# Sheet2_W5500.net
KiCad netlist of a schematic drawn in Altium Designer
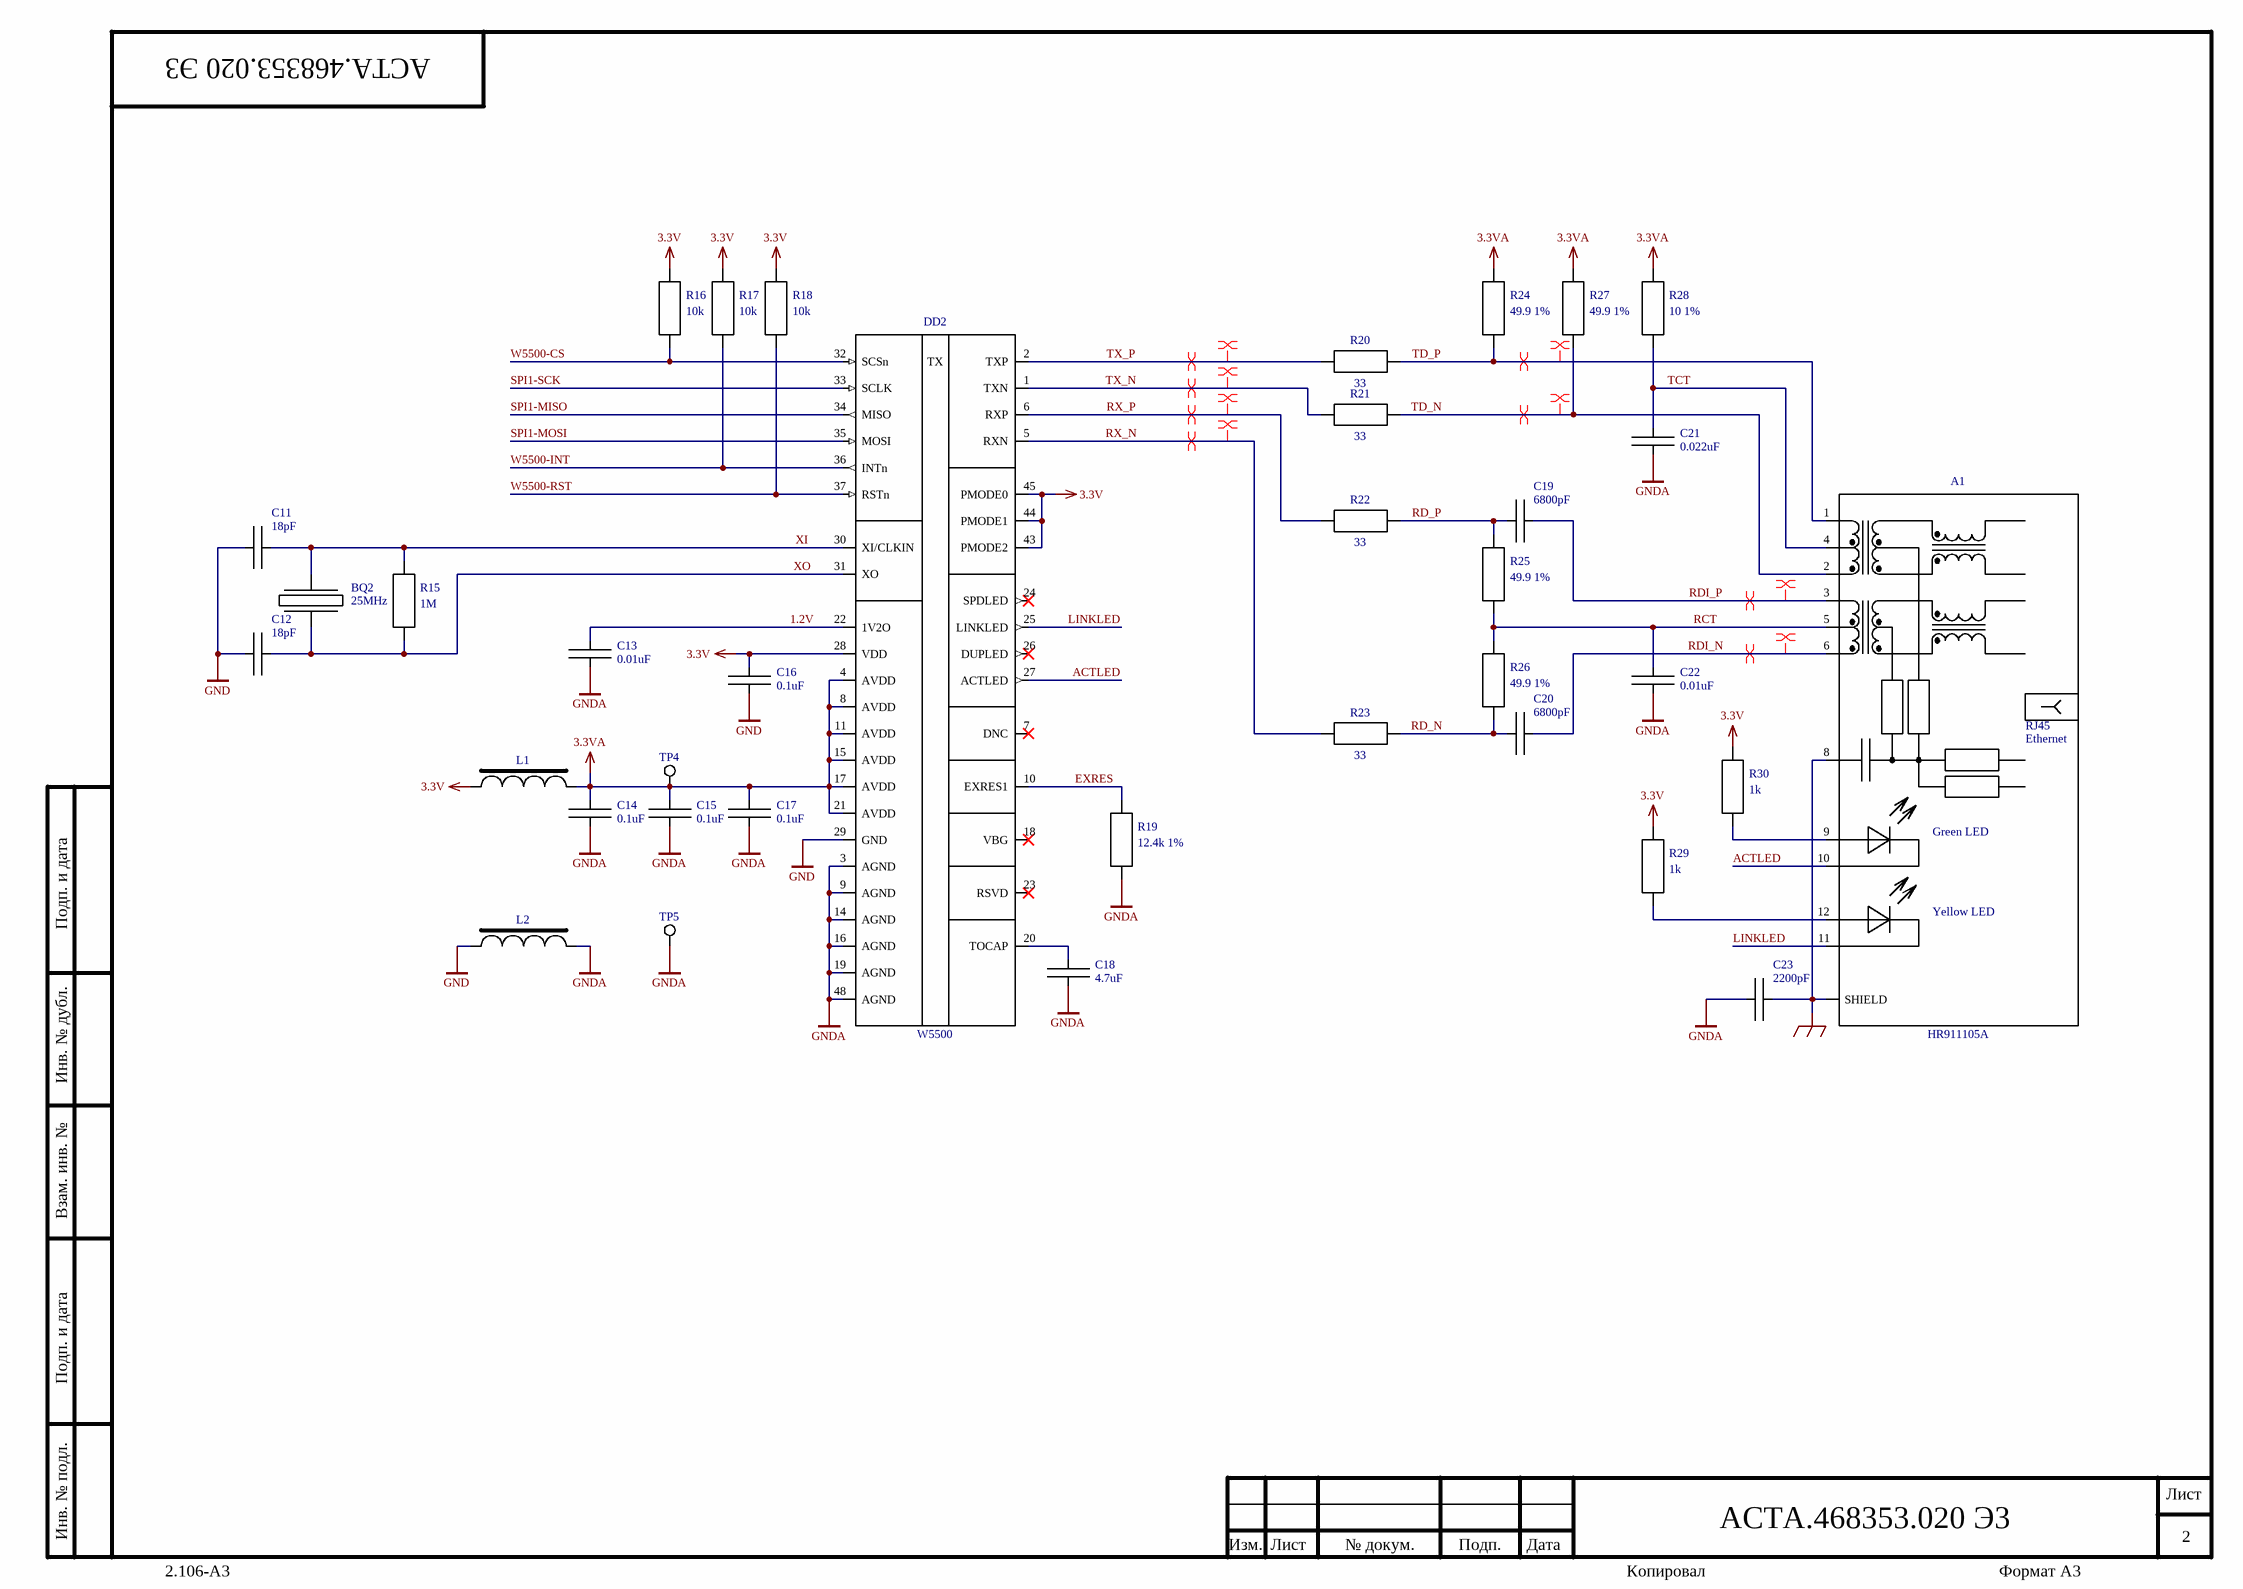
[diagram p0: Sheet2_W5500.SchDoc]

(export (version "E")
  (design (tool "Eeschema 10.0.6"))
  (components
    (comp (ref "A1")
      (value "HR911105A")
      (footprint "HR911105A")
      (description "Ethernet Connector 10/100 1x1 Tab Down RJ45 w/mag G/Y LED")
      (libsource (lib "Devices") (part "HR911105A"))
    )
    (comp (ref "BQ2")
      (value "25MHz")
      (footprint "HT-49S")
      (fields (field (name "Comment") "HT-49S_Rated"))
      (libsource (lib "Resonators") (part "HT-49S_Rated"))
    )
    (comp (ref "C11")
      (value "18pF")
      (footprint "CAP0805")
      (fields (field (name "Comment") "CAP0805_Rated"))
      (libsource (lib "Ceramic_Capacitors") (part "CAP0805_Rated"))
    )
    (comp (ref "C12")
      (value "18pF")
      (footprint "CAP0805")
      (fields (field (name "Comment") "CAP0805_Rated"))
      (libsource (lib "Ceramic_Capacitors") (part "CAP0805_Rated"))
    )
    (comp (ref "C13")
      (value "0.01uF")
      (footprint "CAP0805")
      (fields (field (name "Comment") "CAP0805_Rated"))
      (libsource (lib "Ceramic_Capacitors") (part "CAP0805_Rated"))
    )
    (comp (ref "C14")
      (value "0.1uF")
      (footprint "CAP0805")
      (fields (field (name "Comment") "CAP0805_Rated"))
      (libsource (lib "Ceramic_Capacitors") (part "CAP0805_Rated"))
    )
    (comp (ref "C15")
      (value "0.1uF")
      (footprint "CAP0805")
      (fields (field (name "Comment") "CAP0805_Rated"))
      (libsource (lib "Ceramic_Capacitors") (part "CAP0805_Rated"))
    )
    (comp (ref "C16")
      (value "0.1uF")
      (footprint "CAP0805")
      (fields (field (name "Comment") "CAP0805_Rated"))
      (libsource (lib "Ceramic_Capacitors") (part "CAP0805_Rated"))
    )
    (comp (ref "C17")
      (value "0.1uF")
      (footprint "CAP0805")
      (fields (field (name "Comment") "CAP0805_Rated"))
      (libsource (lib "Ceramic_Capacitors") (part "CAP0805_Rated"))
    )
    (comp (ref "C18")
      (value "4.7uF")
      (footprint "CAP1206")
      (fields (field (name "Comment") "CAP1206_Rated"))
      (libsource (lib "Ceramic_Capacitors") (part "CAP1206_Rated"))
    )
    (comp (ref "C19")
      (value "6800pF")
      (footprint "CAP0805")
      (fields (field (name "Comment") "CAP0805_Rated"))
      (libsource (lib "Ceramic_Capacitors") (part "CAP0805_Rated"))
    )
    (comp (ref "C20")
      (value "6800pF")
      (footprint "CAP0805")
      (fields (field (name "Comment") "CAP0805_Rated"))
      (libsource (lib "Ceramic_Capacitors") (part "CAP0805_Rated"))
    )
    (comp (ref "C21")
      (value "0.022uF")
      (footprint "CAP0805")
      (fields (field (name "Comment") "CAP0805_Rated"))
      (libsource (lib "Ceramic_Capacitors") (part "CAP0805_Rated"))
    )
    (comp (ref "C22")
      (value "0.01uF")
      (footprint "CAP0805")
      (fields (field (name "Comment") "CAP0805_Rated"))
      (libsource (lib "Ceramic_Capacitors") (part "CAP0805_Rated"))
    )
    (comp (ref "C23")
      (value "2200pF")
      (footprint "CAP1812")
      (fields (field (name "Comment") "CAP1812_Rated"))
      (libsource (lib "Ceramic_Capacitors") (part "CAP1812_Rated"))
    )
    (comp (ref "DD2")
      (value "W5500")
      (footprint "LQFP-48")
      (description "Ethernet ICs 3in1 Enet Controller TCP/IP +MAC+PHY")
      (libsource (lib "Interface_ICs") (part "W5500"))
    )
    (comp (ref "L1")
      (value "BLM21BD121SN1D")
      (footprint "IND0805")
      (description "Ferrite Bead 0805 120 Ohm")
      (fields (field (name "MANUFACTURER") "Murata") (field (name "TOLERANCE") "25%"))
      (libsource (lib "Inductors") (part "BLM21BD121SN1D"))
    )
    (comp (ref "L2")
      (value "BLM21BD121SN1D")
      (footprint "IND0805")
      (description "Ferrite Bead 0805 120 Ohm")
      (fields (field (name "MANUFACTURER") "Murata") (field (name "TOLERANCE") "25%"))
      (libsource (lib "Inductors") (part "BLM21BD121SN1D"))
    )
    (comp (ref "R15")
      (value "1M")
      (footprint "RES0805")
      (fields (field (name "TOLERANCE") "5%") (field (name "Comment") "RES0805_Rated"))
      (libsource (lib "Resistors") (part "RES0805_Rated"))
    )
    (comp (ref "R16")
      (value "10k")
      (footprint "RES0805")
      (fields (field (name "TOLERANCE") "5%") (field (name "Comment") "RES0805_Rated"))
      (libsource (lib "Resistors") (part "RES0805_Rated"))
    )
    (comp (ref "R17")
      (value "10k")
      (footprint "RES0805")
      (fields (field (name "TOLERANCE") "5%") (field (name "Comment") "RES0805_Rated"))
      (libsource (lib "Resistors") (part "RES0805_Rated"))
    )
    (comp (ref "R18")
      (value "10k")
      (footprint "RES0805")
      (fields (field (name "TOLERANCE") "5%") (field (name "Comment") "RES0805_Rated"))
      (libsource (lib "Resistors") (part "RES0805_Rated"))
    )
    (comp (ref "R19")
      (value "12.4k 1%")
      (footprint "RES0805")
      (fields (field (name "TOLERANCE") "5%") (field (name "Comment") "RES0805_Rated"))
      (libsource (lib "Resistors") (part "RES0805_Rated"))
    )
    (comp (ref "R20")
      (value "33")
      (footprint "RES0805")
      (fields (field (name "TOLERANCE") "5%") (field (name "Comment") "RES0805_Rated"))
      (libsource (lib "") (part "RES0805_Rated_1"))
    )
    (comp (ref "R21")
      (value "33")
      (footprint "RES0805")
      (fields (field (name "TOLERANCE") "5%") (field (name "Comment") "RES0805_Rated"))
      (libsource (lib "") (part "RES0805_Rated_1"))
    )
    (comp (ref "R22")
      (value "33")
      (footprint "RES0805")
      (fields (field (name "TOLERANCE") "5%") (field (name "Comment") "RES0805_Rated"))
      (libsource (lib "") (part "RES0805_Rated_1"))
    )
    (comp (ref "R23")
      (value "33")
      (footprint "RES0805")
      (fields (field (name "TOLERANCE") "5%") (field (name "Comment") "RES0805_Rated"))
      (libsource (lib "") (part "RES0805_Rated_1"))
    )
    (comp (ref "R24")
      (value "49.9 1%")
      (footprint "RES0805")
      (fields (field (name "TOLERANCE") "5%") (field (name "Comment") "RES0805_Rated"))
      (libsource (lib "Resistors") (part "RES0805_Rated"))
    )
    (comp (ref "R25")
      (value "49.9 1%")
      (footprint "RES0805")
      (fields (field (name "TOLERANCE") "5%") (field (name "Comment") "RES0805_Rated"))
      (libsource (lib "Resistors") (part "RES0805_Rated"))
    )
    (comp (ref "R26")
      (value "49.9 1%")
      (footprint "RES0805")
      (fields (field (name "TOLERANCE") "5%") (field (name "Comment") "RES0805_Rated"))
      (libsource (lib "Resistors") (part "RES0805_Rated"))
    )
    (comp (ref "R27")
      (value "49.9 1%")
      (footprint "RES0805")
      (fields (field (name "TOLERANCE") "5%") (field (name "Comment") "RES0805_Rated"))
      (libsource (lib "Resistors") (part "RES0805_Rated"))
    )
    (comp (ref "R28")
      (value "10 1%")
      (footprint "RES0805")
      (fields (field (name "TOLERANCE") "5%") (field (name "Comment") "RES0805_Rated"))
      (libsource (lib "Resistors") (part "RES0805_Rated"))
    )
    (comp (ref "R29")
      (value "1k")
      (footprint "RES0805")
      (fields (field (name "TOLERANCE") "5%") (field (name "Comment") "RES0805_Rated"))
      (libsource (lib "Resistors") (part "RES0805_Rated"))
    )
    (comp (ref "R30")
      (value "1k")
      (footprint "RES0805")
      (fields (field (name "TOLERANCE") "5%") (field (name "Comment") "RES0805_Rated"))
      (libsource (lib "Resistors") (part "RES0805_Rated"))
    )
    (comp (ref "TP4")
      (value "TestPad")
      (footprint "PAD-TH-OCT1x1-0.5")
      (description "TestPoint on PCB")
      (libsource (lib "Connectors") (part "TestPad"))
    )
    (comp (ref "TP5")
      (value "TestPad")
      (footprint "PAD-TH-OCT1x1-0.5")
      (description "TestPoint on PCB")
      (libsource (lib "Connectors") (part "TestPad"))
    )
  )
  (nets
    (net (code "1") (name "/1.2V") (class "Default")
      (node (ref "C13") (pin "1") (pinfunction "1_1") (pintype "passive"))
      (node (ref "DD2") (pin "22") (pinfunction "1V2O_22") (pintype "power_in"))
    )
    (net (code "2") (name "/ACTLED") (class "Default")
      (node (ref "A1") (pin "10") (pinfunction "LED1-K_10") (pintype "passive"))
      (node (ref "DD2") (pin "27") (pinfunction "ACTLED_27") (pintype "output"))
    )
    (net (code "3") (name "/EXRES") (class "Default")
      (node (ref "DD2") (pin "10") (pinfunction "EXRES1_10") (pintype "passive"))
      (node (ref "R19") (pin "2") (pinfunction "2_2") (pintype "passive"))
    )
    (net (code "4") (name "/LINKLED") (class "Default")
      (node (ref "A1") (pin "11") (pinfunction "LED2-A_11") (pintype "passive"))
      (node (ref "DD2") (pin "25") (pinfunction "LINKLED_25") (pintype "output"))
    )
    (net (code "5") (name "/RCT") (class "Default")
      (node (ref "A1") (pin "5") (pinfunction "CT_5") (pintype "passive"))
      (node (ref "C22") (pin "1") (pinfunction "1_1") (pintype "passive"))
      (node (ref "R25") (pin "1") (pinfunction "1_1") (pintype "passive"))
      (node (ref "R26") (pin "2") (pinfunction "2_2") (pintype "passive"))
    )
    (net (code "6") (name "/RDI_N") (class "Default")
      (node (ref "A1") (pin "6") (pinfunction "RD-_6") (pintype "passive"))
      (node (ref "C20") (pin "2") (pinfunction "2_2") (pintype "passive"))
    )
    (net (code "7") (name "/RDI_P") (class "Default")
      (node (ref "A1") (pin "3") (pinfunction "RD+_3") (pintype "passive"))
      (node (ref "C19") (pin "2") (pinfunction "2_2") (pintype "passive"))
    )
    (net (code "8") (name "/RD_N") (class "Default")
      (node (ref "C20") (pin "1") (pinfunction "1_1") (pintype "passive"))
      (node (ref "R23") (pin "2") (pinfunction "2_2") (pintype "passive"))
      (node (ref "R26") (pin "1") (pinfunction "1_1") (pintype "passive"))
    )
    (net (code "9") (name "/RD_P") (class "Default")
      (node (ref "C19") (pin "1") (pinfunction "1_1") (pintype "passive"))
      (node (ref "R22") (pin "2") (pinfunction "2_2") (pintype "passive"))
      (node (ref "R25") (pin "2") (pinfunction "2_2") (pintype "passive"))
    )
    (net (code "10") (name "/RX_N") (class "Default")
      (node (ref "DD2") (pin "5") (pinfunction "RXN_5") (pintype "passive"))
      (node (ref "R23") (pin "1") (pinfunction "1_1") (pintype "passive"))
    )
    (net (code "11") (name "/RX_P") (class "Default")
      (node (ref "DD2") (pin "6") (pinfunction "RXP_6") (pintype "passive"))
      (node (ref "R22") (pin "1") (pinfunction "1_1") (pintype "passive"))
    )
    (net (code "12") (name "/SPI1-MISO") (class "Default")
      (node (ref "DD2") (pin "34") (pinfunction "MISO_34") (pintype "output"))
    )
    (net (code "13") (name "/SPI1-MOSI") (class "Default")
      (node (ref "DD2") (pin "35") (pinfunction "MOSI_35") (pintype "input"))
    )
    (net (code "14") (name "/SPI1-SCK") (class "Default")
      (node (ref "DD2") (pin "33") (pinfunction "SCLK_33") (pintype "input"))
    )
    (net (code "15") (name "/TCT") (class "Default")
      (node (ref "A1") (pin "4") (pinfunction "CT_4") (pintype "passive"))
      (node (ref "C21") (pin "1") (pinfunction "1_1") (pintype "passive"))
      (node (ref "R28") (pin "1") (pinfunction "1_1") (pintype "passive"))
    )
    (net (code "16") (name "/TD_N") (class "Default")
      (node (ref "A1") (pin "2") (pinfunction "TD-_2") (pintype "passive"))
      (node (ref "R21") (pin "2") (pinfunction "2_2") (pintype "passive"))
      (node (ref "R27") (pin "1") (pinfunction "1_1") (pintype "passive"))
    )
    (net (code "17") (name "/TD_P") (class "Default")
      (node (ref "A1") (pin "1") (pinfunction "TD+_1") (pintype "passive"))
      (node (ref "R20") (pin "2") (pinfunction "2_2") (pintype "passive"))
      (node (ref "R24") (pin "1") (pinfunction "1_1") (pintype "passive"))
    )
    (net (code "18") (name "/TX_N") (class "Default")
      (node (ref "DD2") (pin "1") (pinfunction "TXN_1") (pintype "passive"))
      (node (ref "R21") (pin "1") (pinfunction "1_1") (pintype "passive"))
    )
    (net (code "19") (name "/TX_P") (class "Default")
      (node (ref "DD2") (pin "2") (pinfunction "TXP_2") (pintype "passive"))
      (node (ref "R20") (pin "1") (pinfunction "1_1") (pintype "passive"))
    )
    (net (code "20") (name "/W5500-CS") (class "Default")
      (node (ref "DD2") (pin "32") (pinfunction "SCSn_32") (pintype "input"))
      (node (ref "R16") (pin "1") (pinfunction "1_1") (pintype "passive"))
    )
    (net (code "21") (name "/W5500-INT") (class "Default")
      (node (ref "DD2") (pin "36") (pinfunction "INTn_36") (pintype "output"))
      (node (ref "R17") (pin "1") (pinfunction "1_1") (pintype "passive"))
    )
    (net (code "22") (name "/W5500-RST") (class "Default")
      (node (ref "DD2") (pin "37") (pinfunction "RSTn_37") (pintype "input"))
      (node (ref "R18") (pin "1") (pinfunction "1_1") (pintype "passive"))
    )
    (net (code "23") (name "/XI") (class "Default")
      (node (ref "BQ2") (pin "1") (pinfunction "1_1") (pintype "passive"))
      (node (ref "C11") (pin "2") (pinfunction "2_2") (pintype "passive"))
      (node (ref "DD2") (pin "30") (pinfunction "XI/CLKIN_30") (pintype "passive"))
      (node (ref "R15") (pin "2") (pinfunction "2_2") (pintype "passive"))
    )
    (net (code "24") (name "/XO") (class "Default")
      (node (ref "BQ2") (pin "2") (pinfunction "2_2") (pintype "passive"))
      (node (ref "C12") (pin "2") (pinfunction "2_2") (pintype "passive"))
      (node (ref "DD2") (pin "31") (pinfunction "XO_31") (pintype "passive"))
      (node (ref "R15") (pin "1") (pinfunction "1_1") (pintype "passive"))
    )
    (net (code "25") (name "3.3V") (class "Default")
      (node (ref "C16") (pin "1") (pinfunction "1_1") (pintype "passive"))
      (node (ref "DD2") (pin "28") (pinfunction "VDD_28") (pintype "power_in"))
      (node (ref "DD2") (pin "43") (pinfunction "PMODE2_43") (pintype "passive"))
      (node (ref "DD2") (pin "44") (pinfunction "PMODE1_44") (pintype "passive"))
      (node (ref "DD2") (pin "45") (pinfunction "PMODE0_45") (pintype "passive"))
      (node (ref "L1") (pin "1") (pinfunction "1_1") (pintype "passive"))
      (node (ref "R16") (pin "2") (pinfunction "2_2") (pintype "passive"))
      (node (ref "R17") (pin "2") (pinfunction "2_2") (pintype "passive"))
      (node (ref "R18") (pin "2") (pinfunction "2_2") (pintype "passive"))
      (node (ref "R29") (pin "2") (pinfunction "2_2") (pintype "passive"))
      (node (ref "R30") (pin "2") (pinfunction "2_2") (pintype "passive"))
    )
    (net (code "26") (name "3.3VA") (class "Default")
      (node (ref "C14") (pin "1") (pinfunction "1_1") (pintype "passive"))
      (node (ref "C15") (pin "1") (pinfunction "1_1") (pintype "passive"))
      (node (ref "C17") (pin "1") (pinfunction "1_1") (pintype "passive"))
      (node (ref "DD2") (pin "11") (pinfunction "AVDD_11") (pintype "power_in"))
      (node (ref "DD2") (pin "15") (pinfunction "AVDD_15") (pintype "power_in"))
      (node (ref "DD2") (pin "17") (pinfunction "AVDD_17") (pintype "power_in"))
      (node (ref "DD2") (pin "21") (pinfunction "AVDD_21") (pintype "power_in"))
      (node (ref "DD2") (pin "4") (pinfunction "AVDD_4") (pintype "power_in"))
      (node (ref "DD2") (pin "8") (pinfunction "AVDD_8") (pintype "power_in"))
      (node (ref "L1") (pin "2") (pinfunction "2_2") (pintype "passive"))
      (node (ref "R24") (pin "2") (pinfunction "2_2") (pintype "passive"))
      (node (ref "R27") (pin "2") (pinfunction "2_2") (pintype "passive"))
      (node (ref "R28") (pin "2") (pinfunction "2_2") (pintype "passive"))
      (node (ref "TP4") (pin "1") (pinfunction "1_1") (pintype "passive"))
    )
    (net (code "27") (name "EARTH") (class "Default")
      (node (ref "A1") (pin "8") (pinfunction "GND_8") (pintype "power_in"))
      (node (ref "A1") (pin "SHIELD") (pinfunction "SHIELD_SHIELD") (pintype "passive"))
      (node (ref "C23") (pin "2") (pinfunction "2_2") (pintype "passive"))
    )
    (net (code "28") (name "GND") (class "Default")
      (node (ref "C11") (pin "1") (pinfunction "1_1") (pintype "passive"))
      (node (ref "C12") (pin "1") (pinfunction "1_1") (pintype "passive"))
      (node (ref "C16") (pin "2") (pinfunction "2_2") (pintype "passive"))
      (node (ref "DD2") (pin "29") (pinfunction "GND_29") (pintype "power_in"))
      (node (ref "L2") (pin "1") (pinfunction "1_1") (pintype "passive"))
    )
    (net (code "29") (name "GNDA") (class "Default")
      (node (ref "C13") (pin "2") (pinfunction "2_2") (pintype "passive"))
      (node (ref "C14") (pin "2") (pinfunction "2_2") (pintype "passive"))
      (node (ref "C15") (pin "2") (pinfunction "2_2") (pintype "passive"))
      (node (ref "C17") (pin "2") (pinfunction "2_2") (pintype "passive"))
      (node (ref "C18") (pin "2") (pinfunction "2_2") (pintype "passive"))
      (node (ref "C21") (pin "2") (pinfunction "2_2") (pintype "passive"))
      (node (ref "C22") (pin "2") (pinfunction "2_2") (pintype "passive"))
      (node (ref "C23") (pin "1") (pinfunction "1_1") (pintype "passive"))
      (node (ref "DD2") (pin "14") (pinfunction "AGND_14") (pintype "power_in"))
      (node (ref "DD2") (pin "16") (pinfunction "AGND_16") (pintype "power_in"))
      (node (ref "DD2") (pin "19") (pinfunction "AGND_19") (pintype "power_in"))
      (node (ref "DD2") (pin "3") (pinfunction "AGND_3") (pintype "power_in"))
      (node (ref "DD2") (pin "48") (pinfunction "AGND_48") (pintype "power_in"))
      (node (ref "DD2") (pin "9") (pinfunction "AGND_9") (pintype "power_in"))
      (node (ref "L2") (pin "2") (pinfunction "2_2") (pintype "passive"))
      (node (ref "R19") (pin "1") (pinfunction "1_1") (pintype "passive"))
      (node (ref "TP5") (pin "1") (pinfunction "1_1") (pintype "passive"))
    )
    (net (code "30") (name "Net-(A1-LED1-A)") (class "Default")
      (node (ref "A1") (pin "9") (pinfunction "LED1-A_9") (pintype "passive"))
      (node (ref "R30") (pin "1") (pinfunction "1_1") (pintype "passive"))
    )
    (net (code "31") (name "Net-(A1-LED2-K)") (class "Default")
      (node (ref "A1") (pin "12") (pinfunction "LED2-K_12") (pintype "passive"))
      (node (ref "R29") (pin "1") (pinfunction "1_1") (pintype "passive"))
    )
    (net (code "32") (name "Net-(DD2-TOCAP)") (class "Default")
      (node (ref "C18") (pin "1") (pinfunction "1_1") (pintype "passive"))
      (node (ref "DD2") (pin "20") (pinfunction "TOCAP_20") (pintype "passive"))
    )
    (net (code "33") (name "unconnected-(DD2-DNC-Pad7)") (class "Default")
      (node (ref "DD2") (pin "7") (pinfunction "DNC_7") (pintype "passive+no_connect"))
    )
    (net (code "34") (name "unconnected-(DD2-DUPLED-Pad26)") (class "Default")
      (node (ref "DD2") (pin "26") (pinfunction "DUPLED_26") (pintype "output+no_connect"))
    )
    (net (code "35") (name "unconnected-(DD2-RSVD-Pad23)") (class "Default")
      (node (ref "DD2") (pin "23") (pinfunction "RSVD_23") (pintype "passive+no_connect"))
    )
    (net (code "36") (name "unconnected-(DD2-SPDLED-Pad24)") (class "Default")
      (node (ref "DD2") (pin "24") (pinfunction "SPDLED_24") (pintype "output+no_connect"))
    )
    (net (code "37") (name "unconnected-(DD2-VBG-Pad18)") (class "Default")
      (node (ref "DD2") (pin "18") (pinfunction "VBG_18") (pintype "passive+no_connect"))
    )
  )
)
